# NEAR.net
KiCad netlist of a schematic drawn in Altium Designer
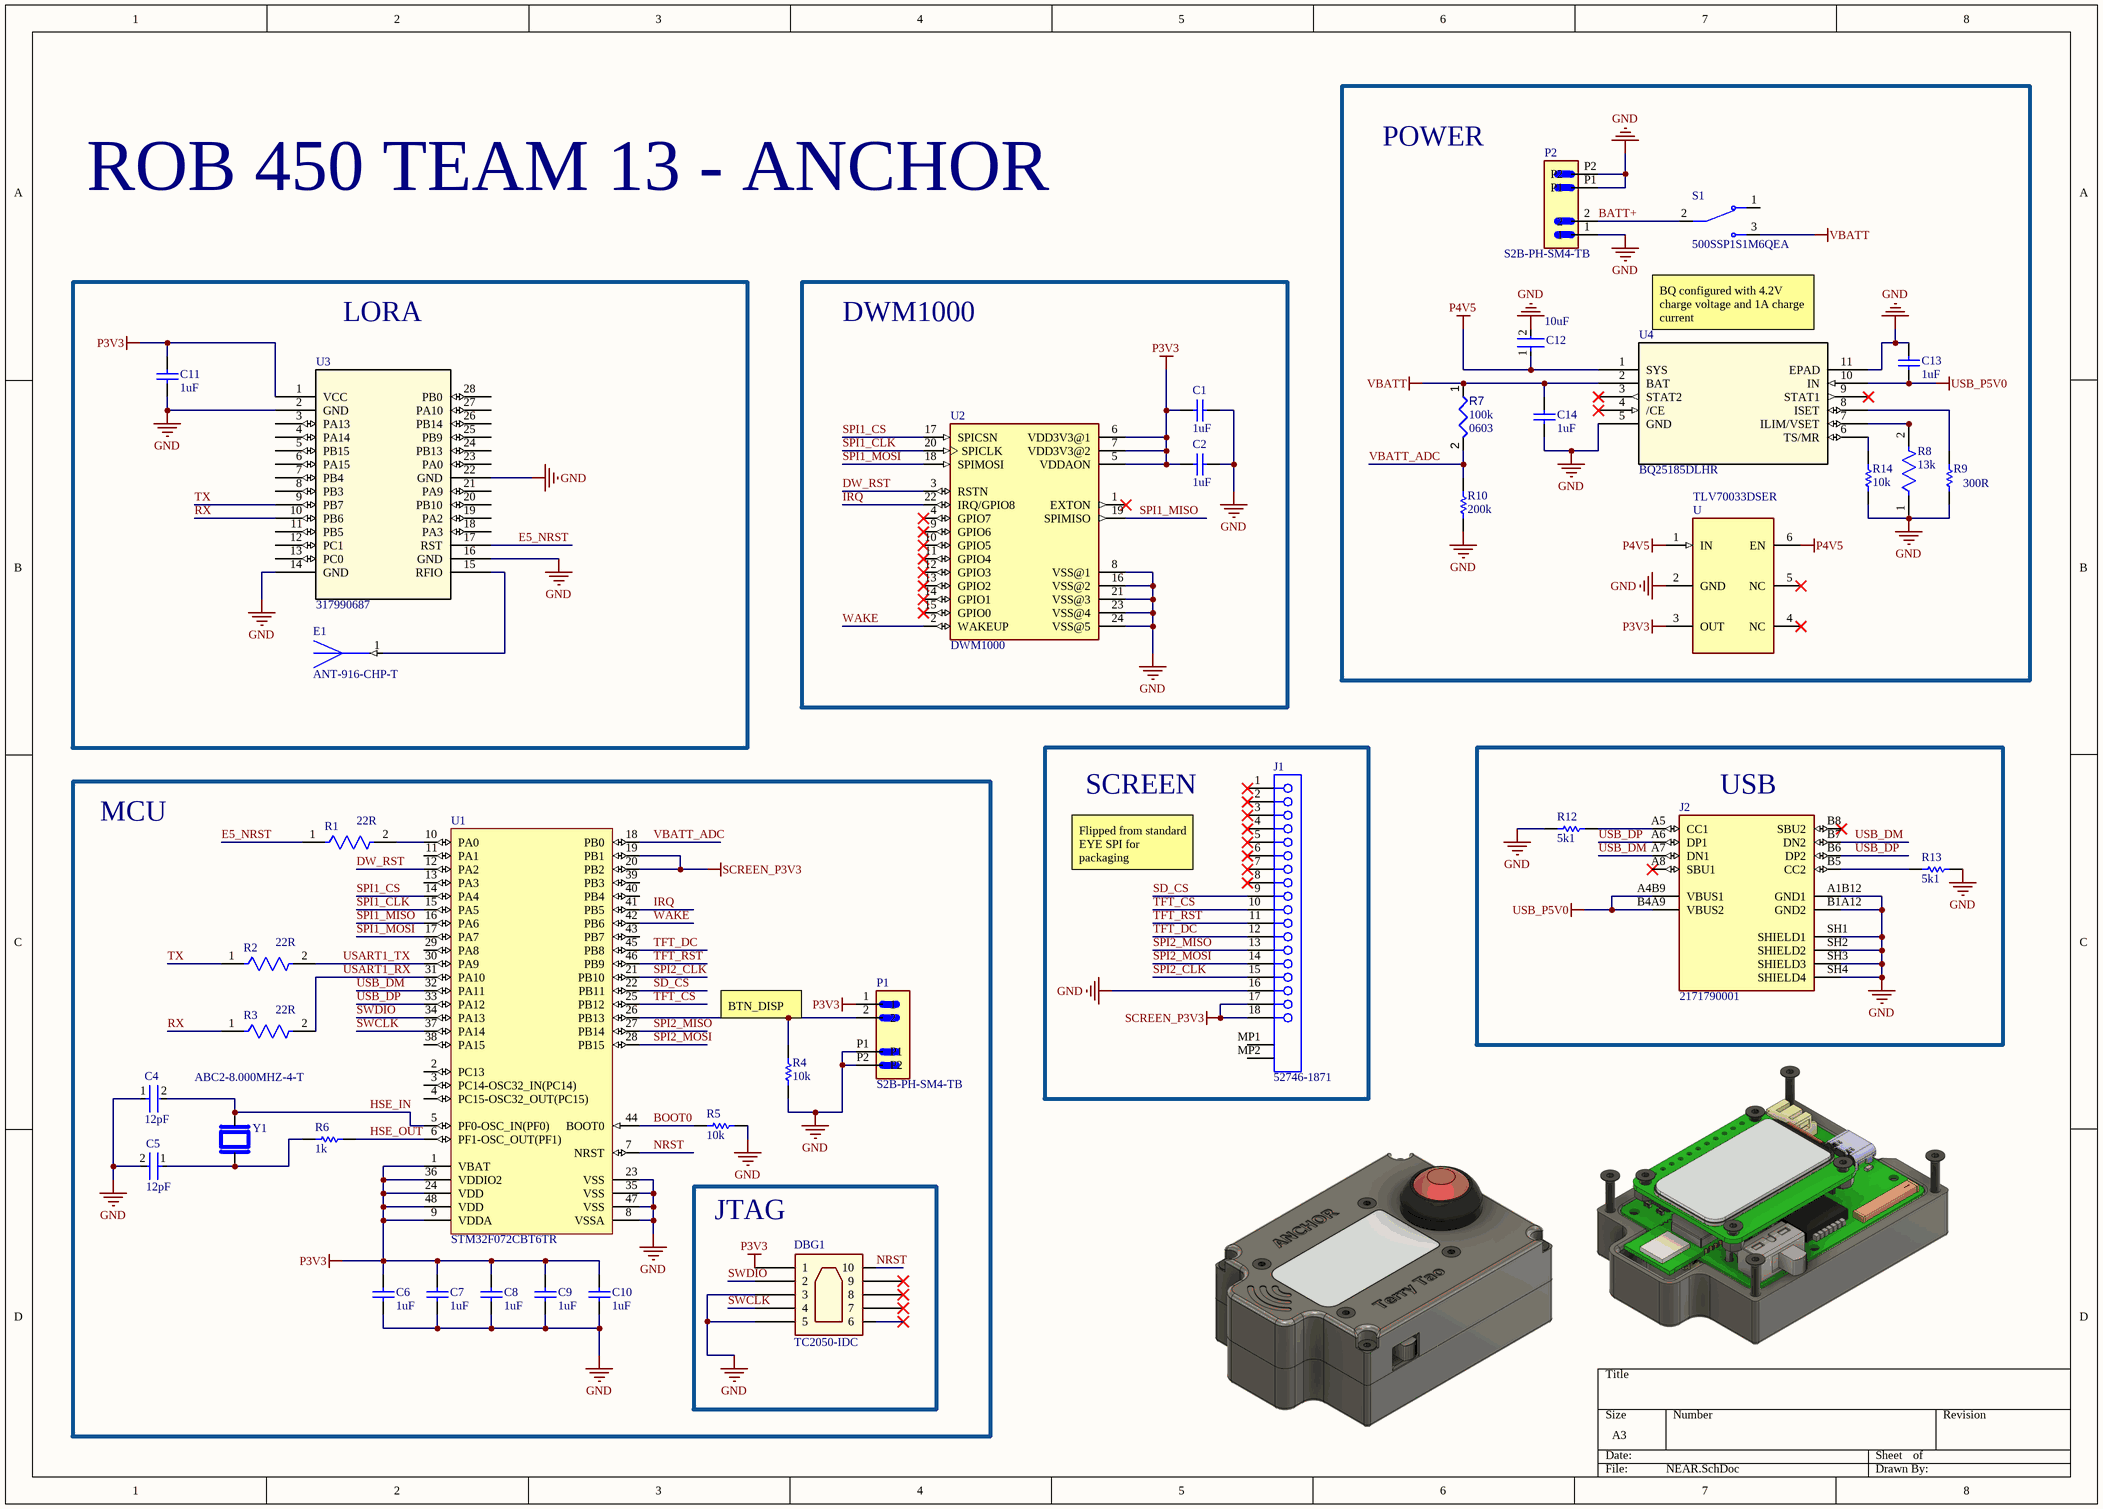
[diagram p0: NEAR.SchDoc]

(export (version "E")
  (design (tool "Eeschema 10.0.6"))
  (components
    (comp (ref "C1")
      (value "1uF")
      (footprint "CAP_0603")
      (description "Cap Ceramic 1uF 25V X7R 10% Pad SMD 0603 125C Automotive T/R")
      (fields (field (name "TOLERANCE") "10%"))
      (libsource (lib "MRacing FSAE") (part "CAP"))
    )
    (comp (ref "C2")
      (value "1uF")
      (footprint "CAP_0603")
      (description "Cap Ceramic 1uF 25V X7R 10% Pad SMD 0603 125C Automotive T/R")
      (fields (field (name "TOLERANCE") "10%"))
      (libsource (lib "MRacing FSAE") (part "CAP"))
    )
    (comp (ref "C4")
      (value "12pF")
      (footprint "FP-C0603C-CF-MFG")
      (description "Ceramic Capacitor 12Pf 50V, C0G, 5%, 0603, Full Reel")
      (fields (field (name "MANUFACTURER") "KEMET") (field (name "TOLERANCE") "0.05"))
      (libsource (lib "Altium Content Vault") (part "b4654b650e69147ec39a6b967a45e02"))
    )
    (comp (ref "C5")
      (value "12pF")
      (footprint "FP-C0603C-CF-MFG")
      (description "Ceramic Capacitor 12Pf 50V, C0G, 5%, 0603, Full Reel")
      (fields (field (name "MANUFACTURER") "KEMET") (field (name "TOLERANCE") "0.05"))
      (libsource (lib "Altium Content Vault") (part "b4654b650e69147ec39a6b967a45e02"))
    )
    (comp (ref "C6")
      (value "1uF")
      (footprint "CAP_0603")
      (description "Cap Ceramic 1uF 25V X7R 10% Pad SMD 0603 125C Automotive T/R")
      (fields (field (name "TOLERANCE") "10%"))
      (libsource (lib "MRacing FSAE") (part "CAP"))
    )
    (comp (ref "C7")
      (value "1uF")
      (footprint "CAP_0603")
      (description "Cap Ceramic 1uF 25V X7R 10% Pad SMD 0603 125C Automotive T/R")
      (fields (field (name "TOLERANCE") "10%"))
      (libsource (lib "MRacing FSAE") (part "CAP"))
    )
    (comp (ref "C8")
      (value "1uF")
      (footprint "CAP_0603")
      (description "Cap Ceramic 1uF 25V X7R 10% Pad SMD 0603 125C Automotive T/R")
      (fields (field (name "TOLERANCE") "10%"))
      (libsource (lib "MRacing FSAE") (part "CAP"))
    )
    (comp (ref "C9")
      (value "1uF")
      (footprint "CAP_0603")
      (description "Cap Ceramic 1uF 25V X7R 10% Pad SMD 0603 125C Automotive T/R")
      (fields (field (name "TOLERANCE") "10%"))
      (libsource (lib "MRacing FSAE") (part "CAP"))
    )
    (comp (ref "C10")
      (value "1uF")
      (footprint "CAP_0603")
      (description "Cap Ceramic 1uF 25V X7R 10% Pad SMD 0603 125C Automotive T/R")
      (fields (field (name "TOLERANCE") "10%"))
      (libsource (lib "MRacing FSAE") (part "CAP"))
    )
    (comp (ref "C11")
      (value "1uF")
      (footprint "CAP_0603")
      (description "Cap Ceramic 1uF 25V X7R 10% Pad SMD 0603 125C Automotive T/R")
      (fields (field (name "TOLERANCE") "10%"))
      (libsource (lib "MRacing FSAE") (part "CAP"))
    )
    (comp (ref "C12")
      (value "10uF")
      (footprint "FP-GRM188-0_1-e0_2_0_55-IPC_A")
      (description "Chip Multilayer Ceramic Capacitors for General Purpose, 0603, 10uF, X5R, 15%, 20%, 6.3V")
      (fields (field (name "VOLTAGE") "6.3V") (field (name "TOLERANCE") "20%"))
      (libsource (lib "Altium Content Vault") (part "02cd4be3c70576c341d710602a673aa"))
    )
    (comp (ref "C13")
      (value "1uF")
      (footprint "CAP_0603")
      (description "Cap Ceramic 1uF 25V X7R 10% Pad SMD 0603 125C Automotive T/R")
      (fields (field (name "TOLERANCE") "10%"))
      (libsource (lib "MRacing FSAE") (part "CAP"))
    )
    (comp (ref "C14")
      (value "1uF")
      (footprint "CAP_0603")
      (description "Cap Ceramic 1uF 25V X7R 10% Pad SMD 0603 125C Automotive T/R")
      (fields (field (name "TOLERANCE") "10%"))
      (libsource (lib "MRacing FSAE") (part "CAP"))
    )
    (comp (ref "DBG1")
      (value "TC2050-IDC")
      (footprint "TC2050-IDC-Footprint-2")
      (description "CBL PLUG-OF-NAILS 10-PIN W/LEGS")
      (libsource (lib "MRacing FSAE") (part "TC2050-IDC-Symbol-1"))
    )
    (comp (ref "E1")
      (value "ANT-916-CHP-T")
      (footprint "XDCR_ANT-916-CHP-T")
      (description "915 MHz Monopole Ceramic Chip Antenna")
      (fields (field (name "MF") "Linx Technologies"))
      (libsource (lib "MRacing FSAE") (part "ANT-916-CHP-T"))
    )
    (comp (ref "J1")
      (value "52746-1871")
      (footprint "MOLX-52746-1871")
      (fields (field (name "MANUFACTURER") "Molex"))
      (libsource (lib "Altium Content Vault") (part "MOLX-52746-1871"))
    )
    (comp (ref "J2")
      (value "2171790001")
      (footprint "MOLEX_2171790001")
      (description "USB Type C - Connector, Top-mount SMT, 16pos")
      (fields (field (name "MP") "217179-0001") (field (name "MF") "Molex"))
      (libsource (lib "MRacing FSAE") (part "2171790001"))
    )
    (comp (ref "P1")
      (value "S2B-PH-SM4-TB")
      (footprint "JST_S2B-PH-SM4-TB")
      (description "Connector Header Surface Mount, Right Angle 2 position 0.079 (2.00mm)")
      (fields (field (name "MF") "JST Sales"))
      (libsource (lib "MRacing FSAE") (part "S2B-PH-SM4-TB"))
    )
    (comp (ref "P2")
      (value "S2B-PH-SM4-TB")
      (footprint "JST_S2B-PH-SM4-TB")
      (description "Connector Header Surface Mount, Right Angle 2 position 0.079 (2.00mm)")
      (fields (field (name "MF") "JST Sales"))
      (libsource (lib "") (part "S2B-PH-SM4-TB_1"))
    )
    (comp (ref "R1")
      (value "22R")
      (footprint "FP-CPF0603-MFG")
      (description "RES SMD 22Ω 0.1% 1/16W 0603")
      (fields
        (field (name "MANUFACTURER") "TE Connectivity")
        (field (name "OCTOPART") "https://octopart.com/cpf0603b22re1-te+connectivity-9539398")
      )
      (libsource (lib "Altium Content Vault") (part "1029c3af85768c4190bb7ad29bc67b5"))
    )
    (comp (ref "R2")
      (value "22R")
      (footprint "FP-CPF0603-MFG")
      (description "RES SMD 22Ω 0.1% 1/16W 0603")
      (fields
        (field (name "MANUFACTURER") "TE Connectivity")
        (field (name "OCTOPART") "https://octopart.com/cpf0603b22re1-te+connectivity-9539398")
      )
      (libsource (lib "Altium Content Vault") (part "1029c3af85768c4190bb7ad29bc67b5"))
    )
    (comp (ref "R3")
      (value "22R")
      (footprint "FP-CPF0603-MFG")
      (description "RES SMD 22Ω 0.1% 1/16W 0603")
      (fields
        (field (name "MANUFACTURER") "TE Connectivity")
        (field (name "OCTOPART") "https://octopart.com/cpf0603b22re1-te+connectivity-9539398")
      )
      (libsource (lib "Altium Content Vault") (part "1029c3af85768c4190bb7ad29bc67b5"))
    )
    (comp (ref "R4")
      (value "10k")
      (footprint "RESC1609X55X30LL15T15")
      (description "Chip Resistor, 10 KOhm, +/- 1%, 0.1 W, -55 to 155 degC, 0603 (1608 Metric), RoHS, Tape and Reel")
      (fields (field (name "TOLERANCE") "1%") (field (name "MANUFACTURER") "Panasonic"))
      (libsource (lib "Altium Content Vault") (part "RES-2"))
    )
    (comp (ref "R5")
      (value "10k")
      (footprint "RESC1609X55X30LL15T15")
      (description "Chip Resistor, 10 KOhm, +/- 1%, 0.1 W, -55 to 155 degC, 0603 (1608 Metric), RoHS, Tape and Reel")
      (fields (field (name "TOLERANCE") "1%") (field (name "MANUFACTURER") "Panasonic"))
      (libsource (lib "Altium Content Vault") (part "RES-2"))
    )
    (comp (ref "R6")
      (value "1k")
      (footprint "RESC1608X55X30LL15T15")
      (fields (field (name "PART NUMBER") "ERJ-3EKF1001V") (field (name "MANUFACTURER") "Panasonic"))
      (libsource (lib "Altium Content Vault") (part "RES"))
    )
    (comp (ref "R7")
      (value "100k")
      (footprint "RESC1608X55X25ML10T15")
      (description "Chip Resistor, 100 KOhm, +/- 1%, 0.1 W, -55 to 155 degC, 0603 (1608 Metric)")
      (fields
        (field (name "POWER") "100mW")
        (field (name "CASE/PACKAGE") "0603")
        (field (name "TOLERANCE") "1%")
      )
      (libsource (lib "MRacing FSAE") (part "RES-2"))
    )
    (comp (ref "R8")
      (value "13k")
      (footprint "FP-ERA3A-IPC_A")
      (description "RES SMD 13K OHM 0.1% 1/10W 0603")
      (fields (field (name "TOLERANCE") "0.1%"))
      (libsource (lib "Altium Content Vault") (part "1029c3af85768c4190bb7ad29bc67b5"))
    )
    (comp (ref "R9")
      (value "300R")
      (footprint "RESC1608X55X30ML15T15")
      (description "ERJ-3GEYJ301V")
      (fields (field (name "MANUFACTURER") "Panasonic"))
      (libsource (lib "Altium Content Vault") (part "RES"))
    )
    (comp (ref "R10")
      (value "200k")
      (footprint "RESC1608X55X25LL10T15")
      (fields (field (name "MANUFACTURER") "Yageo") (field (name "PART NUMBER") "RC0603JR-07200KL"))
      (libsource (lib "Altium Content Vault") (part "RES"))
    )
    (comp (ref "R12")
      (value "5k1")
      (footprint "RESC1608X55X25ML10T15")
      (fields (field (name "MANUFACTURER") "Yageo") (field (name "PART NUMBER") "RC0603FR-075K1L"))
      (libsource (lib "Altium Content Vault") (part "RES"))
    )
    (comp (ref "R13")
      (value "5k1")
      (footprint "RESC1608X55X25ML10T15")
      (fields (field (name "MANUFACTURER") "Yageo") (field (name "PART NUMBER") "RC0603FR-075K1L"))
      (libsource (lib "Altium Content Vault") (part "RES"))
    )
    (comp (ref "R14")
      (value "10k")
      (footprint "RESC1609X55X30LL15T15")
      (description "Chip Resistor, 10 KOhm, +/- 1%, 0.1 W, -55 to 155 degC, 0603 (1608 Metric), RoHS, Tape and Reel")
      (fields (field (name "TOLERANCE") "1%") (field (name "MANUFACTURER") "Panasonic"))
      (libsource (lib "Altium Content Vault") (part "RES-2"))
    )
    (comp (ref "S1")
      (value "500SSP1S1M6QEA")
      (footprint "SW_500SSP1S1M6QEA")
      (description "Slide Switch SPDT Through Hole, Right Angle")
      (fields (field (name "DIGI-KEY_PART_NUMBER") "EG2478-ND") (field (name "MF") "E-Switch"))
      (libsource (lib "MRacing FSAE") (part "500SSP1S1M6QEA"))
    )
    (comp (ref "U")
      (value "TLV70033DSER")
      (footprint "SON50P150X150X80-6N")
      (description "Linear Voltage Regulator IC 1 Output 200mA 6-WSON _1.5x1.5_")
      (fields (field (name "MF") "Texas Instruments"))
      (libsource (lib "MRacing FSAE") (part "TLV70033DSER"))
    )
    (comp (ref "U1")
      (value "STM32F072CBT6TR")
      (footprint "STM-LQFP48_M")
      (libsource (lib "Altium Content Vault") (part "MC-ARM-STM32F07X-LQFP48"))
    )
    (comp (ref "U2")
      (value "DWM1000")
      (footprint "XCVR_DWM1000")
      (description "802.15.4 IR-UWB Transceiver Module 3.5GHz ~ 6.5GHz Integrated, Chip Surface Mount")
      (fields (field (name "MF") "Decawave Limited"))
      (libsource (lib "MRacing FSAE") (part "DWM1000"))
    )
    (comp (ref "U3")
      (value "317990687")
      (footprint "QFN_90687_SEE")
      (description "No Description Available")
      (libsource (lib "MRacing FSAE") (part "317990687"))
    )
    (comp (ref "U4")
      (value "BQ25185DLHR")
      (footprint "WSON10_DLH_TEX")
      (description "No Description Available")
      (libsource (lib "MRacing FSAE") (part "BQ25185DLHR"))
    )
    (comp (ref "Y1")
      (value "ABC2-8.000MHZ-4-T")
      (footprint "XTAL_ABC2-8.000MHZ-4-T")
      (description "LOW FREQUENCY CERAMIC SURFACE MOUNT MICROPROCESSOR CRYSTAL")
      (fields (field (name "MF") "Abracon"))
      (libsource (lib "MRacing FSAE") (part "ABC2-8.000MHZ-4-T"))
    )
  )
  (nets
    (net (code "1") (name "/BATT+") (class "Default")
      (node (ref "P2") (pin "2") (pinfunction "2_2") (pintype "passive"))
      (node (ref "S1") (pin "2") (pinfunction "COM_2") (pintype "passive"))
    )
    (net (code "2") (name "/BOOT0") (class "Default")
      (node (ref "R5") (pin "2") (pinfunction "2_2") (pintype "passive"))
      (node (ref "U1") (pin "44") (pinfunction "BOOT0_44") (pintype "input"))
    )
    (net (code "3") (name "/DW_RST") (class "Default")
      (node (ref "U1") (pin "12") (pinfunction "PA2_12") (pintype "bidirectional"))
      (node (ref "U2") (pin "3") (pinfunction "RSTN_3") (pintype "bidirectional"))
    )
    (net (code "4") (name "/E5_NRST") (class "Default")
      (node (ref "R1") (pin "1") (pinfunction "1_1") (pintype "passive"))
      (node (ref "U3") (pin "17") (pinfunction "RST_17") (pintype "passive"))
    )
    (net (code "5") (name "/HSE_IN") (class "Default")
      (node (ref "C4") (pin "2") (pinfunction "2_2") (pintype "passive"))
      (node (ref "U1") (pin "5") (pinfunction "PF0-OSC_IN(PF0)_5") (pintype "bidirectional"))
      (node (ref "Y1") (pin "2") (pinfunction "2_2") (pintype "passive"))
      (node (ref "Y1") (pin "3") (pinfunction "2_3") (pintype "passive"))
    )
    (net (code "6") (name "/HSE_OUT") (class "Default")
      (node (ref "R6") (pin "1") (pinfunction "1_1") (pintype "passive"))
      (node (ref "U1") (pin "6") (pinfunction "PF1-OSC_OUT(PF1)_6") (pintype "bidirectional"))
    )
    (net (code "7") (name "/IRQ") (class "Default")
      (node (ref "U1") (pin "41") (pinfunction "PB5_41") (pintype "bidirectional"))
      (node (ref "U2") (pin "22") (pinfunction "IRQ/GPIO8_22") (pintype "bidirectional"))
    )
    (net (code "8") (name "/NRST") (class "Default")
      (node (ref "DBG1") (pin "10") (pinfunction "10_10") (pintype "passive"))
      (node (ref "U1") (pin "7") (pinfunction "NRST_7") (pintype "bidirectional"))
    )
    (net (code "9") (name "/RX") (class "Default")
      (node (ref "R3") (pin "1") (pinfunction "1_1") (pintype "passive"))
      (node (ref "U3") (pin "10") (pinfunction "PB6_10") (pintype "bidirectional"))
    )
    (net (code "10") (name "/SD_CS") (class "Default")
      (node (ref "J1") (pin "9") (pinfunction "9_9") (pintype "passive"))
      (node (ref "U1") (pin "22") (pinfunction "PB11_22") (pintype "bidirectional"))
    )
    (net (code "11") (name "/SPI1_CLK") (class "Default")
      (node (ref "U1") (pin "15") (pinfunction "PA5_15") (pintype "bidirectional"))
      (node (ref "U2") (pin "20") (pinfunction "SPICLK_20") (pintype "input"))
    )
    (net (code "12") (name "/SPI1_CS") (class "Default")
      (node (ref "U1") (pin "14") (pinfunction "PA4_14") (pintype "bidirectional"))
      (node (ref "U2") (pin "17") (pinfunction "SPICSN_17") (pintype "input"))
    )
    (net (code "13") (name "/SPI1_MISO") (class "Default")
      (node (ref "U1") (pin "16") (pinfunction "PA6_16") (pintype "bidirectional"))
      (node (ref "U2") (pin "19") (pinfunction "SPIMISO_19") (pintype "output"))
    )
    (net (code "14") (name "/SPI1_MOSI") (class "Default")
      (node (ref "U1") (pin "17") (pinfunction "PA7_17") (pintype "bidirectional"))
      (node (ref "U2") (pin "18") (pinfunction "SPIMOSI_18") (pintype "input"))
    )
    (net (code "15") (name "/SPI2_CLK") (class "Default")
      (node (ref "J1") (pin "15") (pinfunction "15_15") (pintype "passive"))
      (node (ref "U1") (pin "21") (pinfunction "PB10_21") (pintype "bidirectional"))
    )
    (net (code "16") (name "/SPI2_MISO") (class "Default")
      (node (ref "J1") (pin "13") (pinfunction "13_13") (pintype "passive"))
      (node (ref "U1") (pin "27") (pinfunction "PB14_27") (pintype "bidirectional"))
    )
    (net (code "17") (name "/SPI2_MOSI") (class "Default")
      (node (ref "J1") (pin "14") (pinfunction "14_14") (pintype "passive"))
      (node (ref "U1") (pin "28") (pinfunction "PB15_28") (pintype "bidirectional"))
    )
    (net (code "18") (name "/SWCLK") (class "Default")
      (node (ref "DBG1") (pin "4") (pinfunction "4_4") (pintype "passive"))
      (node (ref "U1") (pin "37") (pinfunction "PA14_37") (pintype "bidirectional"))
    )
    (net (code "19") (name "/SWDIO") (class "Default")
      (node (ref "DBG1") (pin "2") (pinfunction "2_2") (pintype "passive"))
      (node (ref "U1") (pin "34") (pinfunction "PA13_34") (pintype "bidirectional"))
    )
    (net (code "20") (name "/TFT_CS") (class "Default")
      (node (ref "J1") (pin "10") (pinfunction "10_10") (pintype "passive"))
      (node (ref "U1") (pin "25") (pinfunction "PB12_25") (pintype "bidirectional"))
    )
    (net (code "21") (name "/TFT_DC") (class "Default")
      (node (ref "J1") (pin "12") (pinfunction "12_12") (pintype "passive"))
      (node (ref "U1") (pin "45") (pinfunction "PB8_45") (pintype "bidirectional"))
    )
    (net (code "22") (name "/TFT_RST") (class "Default")
      (node (ref "J1") (pin "11") (pinfunction "11_11") (pintype "passive"))
      (node (ref "U1") (pin "46") (pinfunction "PB9_46") (pintype "bidirectional"))
    )
    (net (code "23") (name "/TX") (class "Default")
      (node (ref "R2") (pin "1") (pinfunction "1_1") (pintype "passive"))
      (node (ref "U3") (pin "9") (pinfunction "PB7_9") (pintype "bidirectional"))
    )
    (net (code "24") (name "/USART1_RX") (class "Default")
      (node (ref "R3") (pin "2") (pinfunction "2_2") (pintype "passive"))
      (node (ref "U1") (pin "31") (pinfunction "PA10_31") (pintype "bidirectional"))
    )
    (net (code "25") (name "/USART1_TX") (class "Default")
      (node (ref "R2") (pin "2") (pinfunction "2_2") (pintype "passive"))
      (node (ref "U1") (pin "30") (pinfunction "PA9_30") (pintype "bidirectional"))
    )
    (net (code "26") (name "/USB_DM") (class "Default")
      (node (ref "J2") (pin "A7") (pinfunction "DN1_A7") (pintype "bidirectional"))
      (node (ref "J2") (pin "B7") (pinfunction "DN2_B7") (pintype "bidirectional"))
      (node (ref "U1") (pin "32") (pinfunction "PA11_32") (pintype "bidirectional"))
    )
    (net (code "27") (name "/USB_DP") (class "Default")
      (node (ref "J2") (pin "A6") (pinfunction "DP1_A6") (pintype "bidirectional"))
      (node (ref "J2") (pin "B6") (pinfunction "DP2_B6") (pintype "bidirectional"))
      (node (ref "U1") (pin "33") (pinfunction "PA12_33") (pintype "bidirectional"))
    )
    (net (code "28") (name "/VBATT_ADC") (class "Default")
      (node (ref "R10") (pin "1") (pinfunction "1_1") (pintype "passive"))
      (node (ref "R7") (pin "2") (pinfunction "2_2") (pintype "passive"))
      (node (ref "U1") (pin "18") (pinfunction "PB0_18") (pintype "bidirectional"))
    )
    (net (code "29") (name "/WAKE") (class "Default")
      (node (ref "U1") (pin "42") (pinfunction "PB6_42") (pintype "bidirectional"))
      (node (ref "U2") (pin "2") (pinfunction "WAKEUP_2") (pintype "bidirectional"))
    )
    (net (code "30") (name "GND") (class "Default")
      (node (ref "C1") (pin "2") (pinfunction "2_2") (pintype "passive"))
      (node (ref "C10") (pin "1") (pinfunction "1_1") (pintype "passive"))
      (node (ref "C11") (pin "1") (pinfunction "1_1") (pintype "passive"))
      (node (ref "C12") (pin "2") (pinfunction "2_2") (pintype "passive"))
      (node (ref "C13") (pin "2") (pinfunction "2_2") (pintype "passive"))
      (node (ref "C14") (pin "1") (pinfunction "1_1") (pintype "passive"))
      (node (ref "C2") (pin "2") (pinfunction "2_2") (pintype "passive"))
      (node (ref "C4") (pin "1") (pinfunction "1_1") (pintype "passive"))
      (node (ref "C5") (pin "2") (pinfunction "2_2") (pintype "passive"))
      (node (ref "C6") (pin "1") (pinfunction "1_1") (pintype "passive"))
      (node (ref "C7") (pin "1") (pinfunction "1_1") (pintype "passive"))
      (node (ref "C8") (pin "1") (pinfunction "1_1") (pintype "passive"))
      (node (ref "C9") (pin "1") (pinfunction "1_1") (pintype "passive"))
      (node (ref "DBG1") (pin "3") (pinfunction "3_3") (pintype "passive"))
      (node (ref "DBG1") (pin "5") (pinfunction "5_5") (pintype "passive"))
      (node (ref "J1") (pin "16") (pinfunction "16_16") (pintype "passive"))
      (node (ref "J2") (pin "A1B12") (pinfunction "GND1_A1B12") (pintype "power_in"))
      (node (ref "J2") (pin "B1A12") (pinfunction "GND2_B1A12") (pintype "power_in"))
      (node (ref "J2") (pin "SH1") (pinfunction "SHIELD1_SH1") (pintype "passive"))
      (node (ref "J2") (pin "SH2") (pinfunction "SHIELD2_SH2") (pintype "passive"))
      (node (ref "J2") (pin "SH3") (pinfunction "SHIELD3_SH3") (pintype "passive"))
      (node (ref "J2") (pin "SH4") (pinfunction "SHIELD4_SH4") (pintype "passive"))
      (node (ref "P1") (pin "P1") (pinfunction "P1_P1") (pintype "passive"))
      (node (ref "P1") (pin "P2") (pinfunction "P2_P2") (pintype "passive"))
      (node (ref "P2") (pin "1") (pinfunction "1_1") (pintype "passive"))
      (node (ref "P2") (pin "P1") (pinfunction "P1_P1") (pintype "passive"))
      (node (ref "P2") (pin "P2") (pinfunction "P2_P2") (pintype "passive"))
      (node (ref "R10") (pin "2") (pinfunction "2_2") (pintype "passive"))
      (node (ref "R12") (pin "2") (pinfunction "2_2") (pintype "passive"))
      (node (ref "R13") (pin "1") (pinfunction "1_1") (pintype "passive"))
      (node (ref "R14") (pin "1") (pinfunction "1_1") (pintype "passive"))
      (node (ref "R4") (pin "1") (pinfunction "1_1") (pintype "passive"))
      (node (ref "R5") (pin "1") (pinfunction "1_1") (pintype "passive"))
      (node (ref "R8") (pin "1") (pinfunction "1_1") (pintype "passive"))
      (node (ref "R9") (pin "2") (pinfunction "2_2") (pintype "passive"))
      (node (ref "U") (pin "2") (pinfunction "GND_2") (pintype "power_in"))
      (node (ref "U1") (pin "23") (pinfunction "VSS_23") (pintype "power_in"))
      (node (ref "U1") (pin "35") (pinfunction "VSS_35") (pintype "power_in"))
      (node (ref "U1") (pin "47") (pinfunction "VSS_47") (pintype "power_in"))
      (node (ref "U1") (pin "8") (pinfunction "VSSA_8") (pintype "power_in"))
      (node (ref "U2") (pin "16") (pinfunction "VSS@2_16") (pintype "power_in"))
      (node (ref "U2") (pin "21") (pinfunction "VSS@3_21") (pintype "power_in"))
      (node (ref "U2") (pin "23") (pinfunction "VSS@4_23") (pintype "power_in"))
      (node (ref "U2") (pin "24") (pinfunction "VSS@5_24") (pintype "power_in"))
      (node (ref "U2") (pin "8") (pinfunction "VSS@1_8") (pintype "power_in"))
      (node (ref "U3") (pin "14") (pinfunction "GND_14") (pintype "power_in"))
      (node (ref "U3") (pin "16") (pinfunction "GND_16") (pintype "power_in"))
      (node (ref "U3") (pin "2") (pinfunction "GND_2") (pintype "power_in"))
      (node (ref "U3") (pin "22") (pinfunction "GND_22") (pintype "power_in"))
      (node (ref "U4") (pin "11") (pinfunction "EPAD_11") (pintype "passive"))
      (node (ref "U4") (pin "5") (pinfunction "GND_5") (pintype "power_in"))
    )
    (net (code "31") (name "Net-(C5-Pad1)") (class "Default")
      (node (ref "C5") (pin "1") (pinfunction "1_1") (pintype "passive"))
      (node (ref "R6") (pin "2") (pinfunction "2_2") (pintype "passive"))
      (node (ref "Y1") (pin "1") (pinfunction "1_1") (pintype "passive"))
      (node (ref "Y1") (pin "4") (pinfunction "1_4") (pintype "passive"))
    )
    (net (code "32") (name "Net-(E1-FEED)") (class "Default")
      (node (ref "E1") (pin "1") (pinfunction "FEED_1") (pintype "input"))
      (node (ref "U3") (pin "15") (pinfunction "RFIO_15") (pintype "passive"))
    )
    (net (code "33") (name "Net-(J2-CC1)") (class "Default")
      (node (ref "J2") (pin "A5") (pinfunction "CC1_A5") (pintype "bidirectional"))
      (node (ref "R12") (pin "1") (pinfunction "1_1") (pintype "passive"))
    )
    (net (code "34") (name "Net-(J2-CC2)") (class "Default")
      (node (ref "J2") (pin "B5") (pinfunction "CC2_B5") (pintype "bidirectional"))
      (node (ref "R13") (pin "2") (pinfunction "2_2") (pintype "passive"))
    )
    (net (code "35") (name "Net-(U1-PA0)") (class "Default")
      (node (ref "R1") (pin "2") (pinfunction "2_2") (pintype "passive"))
      (node (ref "U1") (pin "10") (pinfunction "PA0_10") (pintype "bidirectional"))
    )
    (net (code "36") (name "Net-(U1-PB13)") (class "Default")
      (node (ref "P1") (pin "2") (pinfunction "2_2") (pintype "passive"))
      (node (ref "R4") (pin "2") (pinfunction "2_2") (pintype "passive"))
      (node (ref "U1") (pin "26") (pinfunction "PB13_26") (pintype "bidirectional"))
    )
    (net (code "37") (name "Net-(U4-ILIM{slash}VSET)") (class "Default")
      (node (ref "R8") (pin "2") (pinfunction "2_2") (pintype "passive"))
      (node (ref "U4") (pin "7") (pinfunction "ILIM/VSET_7") (pintype "bidirectional"))
    )
    (net (code "38") (name "Net-(U4-ISET)") (class "Default")
      (node (ref "R9") (pin "1") (pinfunction "1_1") (pintype "passive"))
      (node (ref "U4") (pin "8") (pinfunction "ISET_8") (pintype "bidirectional"))
    )
    (net (code "39") (name "Net-(U4-TS{slash}MR)") (class "Default")
      (node (ref "R14") (pin "2") (pinfunction "2_2") (pintype "passive"))
      (node (ref "U4") (pin "6") (pinfunction "TS/MR_6") (pintype "bidirectional"))
    )
    (net (code "40") (name "P3V3") (class "Default")
      (node (ref "C1") (pin "1") (pinfunction "1_1") (pintype "passive"))
      (node (ref "C10") (pin "2") (pinfunction "2_2") (pintype "passive"))
      (node (ref "C11") (pin "2") (pinfunction "2_2") (pintype "passive"))
      (node (ref "C2") (pin "1") (pinfunction "1_1") (pintype "passive"))
      (node (ref "C6") (pin "2") (pinfunction "2_2") (pintype "passive"))
      (node (ref "C7") (pin "2") (pinfunction "2_2") (pintype "passive"))
      (node (ref "C8") (pin "2") (pinfunction "2_2") (pintype "passive"))
      (node (ref "C9") (pin "2") (pinfunction "2_2") (pintype "passive"))
      (node (ref "DBG1") (pin "1") (pinfunction "1_1") (pintype "passive"))
      (node (ref "P1") (pin "1") (pinfunction "1_1") (pintype "passive"))
      (node (ref "U") (pin "3") (pinfunction "OUT_3") (pintype "power_in"))
      (node (ref "U1") (pin "1") (pinfunction "VBAT_1") (pintype "power_in"))
      (node (ref "U1") (pin "24") (pinfunction "VDD_24") (pintype "power_in"))
      (node (ref "U1") (pin "36") (pinfunction "VDDIO2_36") (pintype "power_in"))
      (node (ref "U1") (pin "48") (pinfunction "VDD_48") (pintype "power_in"))
      (node (ref "U1") (pin "9") (pinfunction "VDDA_9") (pintype "power_in"))
      (node (ref "U2") (pin "5") (pinfunction "VDDAON_5") (pintype "power_in"))
      (node (ref "U2") (pin "6") (pinfunction "VDD3V3@1_6") (pintype "power_in"))
      (node (ref "U2") (pin "7") (pinfunction "VDD3V3@2_7") (pintype "power_in"))
      (node (ref "U3") (pin "1") (pinfunction "VCC_1") (pintype "power_in"))
    )
    (net (code "41") (name "P4V5") (class "Default")
      (node (ref "C12") (pin "1") (pinfunction "1_1") (pintype "passive"))
      (node (ref "U") (pin "1") (pinfunction "IN_1") (pintype "input"))
      (node (ref "U") (pin "6") (pinfunction "EN_6") (pintype "power_in"))
      (node (ref "U4") (pin "1") (pinfunction "SYS_1") (pintype "power_in"))
    )
    (net (code "42") (name "SCREEN_P3V3") (class "Default")
      (node (ref "J1") (pin "17") (pinfunction "17_17") (pintype "passive"))
      (node (ref "J1") (pin "18") (pinfunction "18_18") (pintype "passive"))
      (node (ref "U1") (pin "19") (pinfunction "PB1_19") (pintype "bidirectional"))
      (node (ref "U1") (pin "20") (pinfunction "PB2_20") (pintype "bidirectional"))
    )
    (net (code "43") (name "USB_P5V0") (class "Default")
      (node (ref "C13") (pin "1") (pinfunction "1_1") (pintype "passive"))
      (node (ref "J2") (pin "A4B9") (pinfunction "VBUS1_A4B9") (pintype "power_in"))
      (node (ref "J2") (pin "B4A9") (pinfunction "VBUS2_B4A9") (pintype "power_in"))
      (node (ref "U4") (pin "10") (pinfunction "IN_10") (pintype "input"))
    )
    (net (code "44") (name "VBATT") (class "Default")
      (node (ref "C14") (pin "2") (pinfunction "2_2") (pintype "passive"))
      (node (ref "R7") (pin "1") (pinfunction "1_1") (pintype "passive"))
      (node (ref "S1") (pin "3") (pinfunction "NO_3") (pintype "passive"))
      (node (ref "U4") (pin "2") (pinfunction "BAT_2") (pintype "power_in"))
    )
    (net (code "45") (name "unconnected-(DBG1-Pad6)") (class "Default")
      (node (ref "DBG1") (pin "6") (pinfunction "6_6") (pintype "passive+no_connect"))
    )
    (net (code "46") (name "unconnected-(DBG1-Pad7)") (class "Default")
      (node (ref "DBG1") (pin "7") (pinfunction "7_7") (pintype "passive+no_connect"))
    )
    (net (code "47") (name "unconnected-(DBG1-Pad8)") (class "Default")
      (node (ref "DBG1") (pin "8") (pinfunction "8_8") (pintype "passive+no_connect"))
    )
    (net (code "48") (name "unconnected-(DBG1-Pad9)") (class "Default")
      (node (ref "DBG1") (pin "9") (pinfunction "9_9") (pintype "passive+no_connect"))
    )
    (net (code "49") (name "unconnected-(J1-Pad1)") (class "Default")
      (node (ref "J1") (pin "1") (pinfunction "1_1") (pintype "passive+no_connect"))
    )
    (net (code "50") (name "unconnected-(J1-Pad2)") (class "Default")
      (node (ref "J1") (pin "2") (pinfunction "2_2") (pintype "passive+no_connect"))
    )
    (net (code "51") (name "unconnected-(J1-Pad3)") (class "Default")
      (node (ref "J1") (pin "3") (pinfunction "3_3") (pintype "passive+no_connect"))
    )
    (net (code "52") (name "unconnected-(J1-Pad4)") (class "Default")
      (node (ref "J1") (pin "4") (pinfunction "4_4") (pintype "passive+no_connect"))
    )
    (net (code "53") (name "unconnected-(J1-Pad5)") (class "Default")
      (node (ref "J1") (pin "5") (pinfunction "5_5") (pintype "passive+no_connect"))
    )
    (net (code "54") (name "unconnected-(J1-Pad6)") (class "Default")
      (node (ref "J1") (pin "6") (pinfunction "6_6") (pintype "passive+no_connect"))
    )
    (net (code "55") (name "unconnected-(J1-Pad7)") (class "Default")
      (node (ref "J1") (pin "7") (pinfunction "7_7") (pintype "passive+no_connect"))
    )
    (net (code "56") (name "unconnected-(J1-Pad8)") (class "Default")
      (node (ref "J1") (pin "8") (pinfunction "8_8") (pintype "passive+no_connect"))
    )
    (net (code "57") (name "unconnected-(J1-PadMP1)") (class "Default")
      (node (ref "J1") (pin "MP1") (pinfunction "MP1_MP1") (pintype "passive"))
    )
    (net (code "58") (name "unconnected-(J1-PadMP2)") (class "Default")
      (node (ref "J1") (pin "MP2") (pinfunction "MP2_MP2") (pintype "passive"))
    )
    (net (code "59") (name "unconnected-(J2-SBU1-PadA8)") (class "Default")
      (node (ref "J2") (pin "A8") (pinfunction "SBU1_A8") (pintype "bidirectional+no_connect"))
    )
    (net (code "60") (name "unconnected-(J2-SBU2-PadB8)") (class "Default")
      (node (ref "J2") (pin "B8") (pinfunction "SBU2_B8") (pintype "bidirectional+no_connect"))
    )
    (net (code "61") (name "unconnected-(S1-NC-Pad1)") (class "Default")
      (node (ref "S1") (pin "1") (pinfunction "NC_1") (pintype "passive"))
    )
    (net (code "62") (name "unconnected-(U-NC-Pad4)") (class "Default")
      (node (ref "U") (pin "4") (pinfunction "NC_4") (pintype "power_in+no_connect"))
    )
    (net (code "63") (name "unconnected-(U-NC-Pad5)") (class "Default")
      (node (ref "U") (pin "5") (pinfunction "NC_5") (pintype "power_in+no_connect"))
    )
    (net (code "64") (name "unconnected-(U1-PA1-Pad11)") (class "Default")
      (node (ref "U1") (pin "11") (pinfunction "PA1_11") (pintype "bidirectional"))
    )
    (net (code "65") (name "unconnected-(U1-PA3-Pad13)") (class "Default")
      (node (ref "U1") (pin "13") (pinfunction "PA3_13") (pintype "bidirectional"))
    )
    (net (code "66") (name "unconnected-(U1-PA8-Pad29)") (class "Default")
      (node (ref "U1") (pin "29") (pinfunction "PA8_29") (pintype "bidirectional"))
    )
    (net (code "67") (name "unconnected-(U1-PA15-Pad38)") (class "Default")
      (node (ref "U1") (pin "38") (pinfunction "PA15_38") (pintype "bidirectional"))
    )
    (net (code "68") (name "unconnected-(U1-PB3-Pad39)") (class "Default")
      (node (ref "U1") (pin "39") (pinfunction "PB3_39") (pintype "bidirectional"))
    )
    (net (code "69") (name "unconnected-(U1-PB4-Pad40)") (class "Default")
      (node (ref "U1") (pin "40") (pinfunction "PB4_40") (pintype "bidirectional"))
    )
    (net (code "70") (name "unconnected-(U1-PB7-Pad43)") (class "Default")
      (node (ref "U1") (pin "43") (pinfunction "PB7_43") (pintype "bidirectional"))
    )
    (net (code "71") (name "unconnected-(U1-PC13-Pad2)") (class "Default")
      (node (ref "U1") (pin "2") (pinfunction "PC13_2") (pintype "bidirectional"))
    )
    (net (code "72") (name "unconnected-(U1-PC14-OSC32_IN(PC14)-Pad3)") (class "Default")
      (node (ref "U1") (pin "3") (pinfunction "PC14-OSC32_IN(PC14)_3") (pintype "bidirectional"))
    )
    (net (code "73") (name "unconnected-(U1-PC15-OSC32_OUT(PC15)-Pad4)") (class "Default")
      (node (ref "U1") (pin "4") (pinfunction "PC15-OSC32_OUT(PC15)_4") (pintype "bidirectional"))
    )
    (net (code "74") (name "unconnected-(U2-EXTON-Pad1)") (class "Default")
      (node (ref "U2") (pin "1") (pinfunction "EXTON_1") (pintype "output+no_connect"))
    )
    (net (code "75") (name "unconnected-(U2-GPIO0-Pad15)") (class "Default")
      (node (ref "U2") (pin "15") (pinfunction "GPIO0_15") (pintype "bidirectional+no_connect"))
    )
    (net (code "76") (name "unconnected-(U2-GPIO1-Pad14)") (class "Default")
      (node (ref "U2") (pin "14") (pinfunction "GPIO1_14") (pintype "bidirectional+no_connect"))
    )
    (net (code "77") (name "unconnected-(U2-GPIO2-Pad13)") (class "Default")
      (node (ref "U2") (pin "13") (pinfunction "GPIO2_13") (pintype "bidirectional+no_connect"))
    )
    (net (code "78") (name "unconnected-(U2-GPIO3-Pad12)") (class "Default")
      (node (ref "U2") (pin "12") (pinfunction "GPIO3_12") (pintype "bidirectional+no_connect"))
    )
    (net (code "79") (name "unconnected-(U2-GPIO4-Pad11)") (class "Default")
      (node (ref "U2") (pin "11") (pinfunction "GPIO4_11") (pintype "bidirectional+no_connect"))
    )
    (net (code "80") (name "unconnected-(U2-GPIO5-Pad10)") (class "Default")
      (node (ref "U2") (pin "10") (pinfunction "GPIO5_10") (pintype "bidirectional+no_connect"))
    )
    (net (code "81") (name "unconnected-(U2-GPIO6-Pad9)") (class "Default")
      (node (ref "U2") (pin "9") (pinfunction "GPIO6_9") (pintype "bidirectional+no_connect"))
    )
    (net (code "82") (name "unconnected-(U2-GPIO7-Pad4)") (class "Default")
      (node (ref "U2") (pin "4") (pinfunction "GPIO7_4") (pintype "bidirectional+no_connect"))
    )
    (net (code "83") (name "unconnected-(U3-PA0-Pad23)") (class "Default")
      (node (ref "U3") (pin "23") (pinfunction "PA0_23") (pintype "bidirectional"))
    )
    (net (code "84") (name "unconnected-(U3-PA2-Pad19)") (class "Default")
      (node (ref "U3") (pin "19") (pinfunction "PA2_19") (pintype "bidirectional"))
    )
    (net (code "85") (name "unconnected-(U3-PA3-Pad18)") (class "Default")
      (node (ref "U3") (pin "18") (pinfunction "PA3_18") (pintype "bidirectional"))
    )
    (net (code "86") (name "unconnected-(U3-PA9-Pad21)") (class "Default")
      (node (ref "U3") (pin "21") (pinfunction "PA9_21") (pintype "bidirectional"))
    )
    (net (code "87") (name "unconnected-(U3-PA10-Pad27)") (class "Default")
      (node (ref "U3") (pin "27") (pinfunction "PA10_27") (pintype "bidirectional"))
    )
    (net (code "88") (name "unconnected-(U3-PA13-Pad3)") (class "Default")
      (node (ref "U3") (pin "3") (pinfunction "PA13_3") (pintype "bidirectional"))
    )
    (net (code "89") (name "unconnected-(U3-PA14-Pad4)") (class "Default")
      (node (ref "U3") (pin "4") (pinfunction "PA14_4") (pintype "bidirectional"))
    )
    (net (code "90") (name "unconnected-(U3-PA15-Pad6)") (class "Default")
      (node (ref "U3") (pin "6") (pinfunction "PA15_6") (pintype "bidirectional"))
    )
    (net (code "91") (name "unconnected-(U3-PB0-Pad28)") (class "Default")
      (node (ref "U3") (pin "28") (pinfunction "PB0_28") (pintype "bidirectional"))
    )
    (net (code "92") (name "unconnected-(U3-PB3-Pad8)") (class "Default")
      (node (ref "U3") (pin "8") (pinfunction "PB3_8") (pintype "bidirectional"))
    )
    (net (code "93") (name "unconnected-(U3-PB4-Pad7)") (class "Default")
      (node (ref "U3") (pin "7") (pinfunction "PB4_7") (pintype "bidirectional"))
    )
    (net (code "94") (name "unconnected-(U3-PB5-Pad11)") (class "Default")
      (node (ref "U3") (pin "11") (pinfunction "PB5_11") (pintype "bidirectional"))
    )
    (net (code "95") (name "unconnected-(U3-PB9-Pad25)") (class "Default")
      (node (ref "U3") (pin "25") (pinfunction "PB9_25") (pintype "bidirectional"))
    )
    (net (code "96") (name "unconnected-(U3-PB10-Pad20)") (class "Default")
      (node (ref "U3") (pin "20") (pinfunction "PB10_20") (pintype "bidirectional"))
    )
    (net (code "97") (name "unconnected-(U3-PB13-Pad24)") (class "Default")
      (node (ref "U3") (pin "24") (pinfunction "PB13_24") (pintype "bidirectional"))
    )
    (net (code "98") (name "unconnected-(U3-PB14-Pad26)") (class "Default")
      (node (ref "U3") (pin "26") (pinfunction "PB14_26") (pintype "bidirectional"))
    )
    (net (code "99") (name "unconnected-(U3-PB15-Pad5)") (class "Default")
      (node (ref "U3") (pin "5") (pinfunction "PB15_5") (pintype "bidirectional"))
    )
    (net (code "100") (name "unconnected-(U3-PC0-Pad13)") (class "Default")
      (node (ref "U3") (pin "13") (pinfunction "PC0_13") (pintype "bidirectional"))
    )
    (net (code "101") (name "unconnected-(U3-PC1-Pad12)") (class "Default")
      (node (ref "U3") (pin "12") (pinfunction "PC1_12") (pintype "bidirectional"))
    )
    (net (code "102") (name "unconnected-(U4-STAT1-Pad9)") (class "Default")
      (node (ref "U4") (pin "9") (pinfunction "STAT1_9") (pintype "output+no_connect"))
    )
    (net (code "103") (name "unconnected-(U4-STAT2-Pad3)") (class "Default")
      (node (ref "U4") (pin "3") (pinfunction "STAT2_3") (pintype "output+no_connect"))
    )
    (net (code "104") (name "unconnected-(U4-{slash}CE-Pad4)") (class "Default")
      (node (ref "U4") (pin "4") (pinfunction "/CE_4") (pintype "input+no_connect"))
    )
  )
)
